# M2.net
KiCad netlist of a schematic drawn in Altium Designer
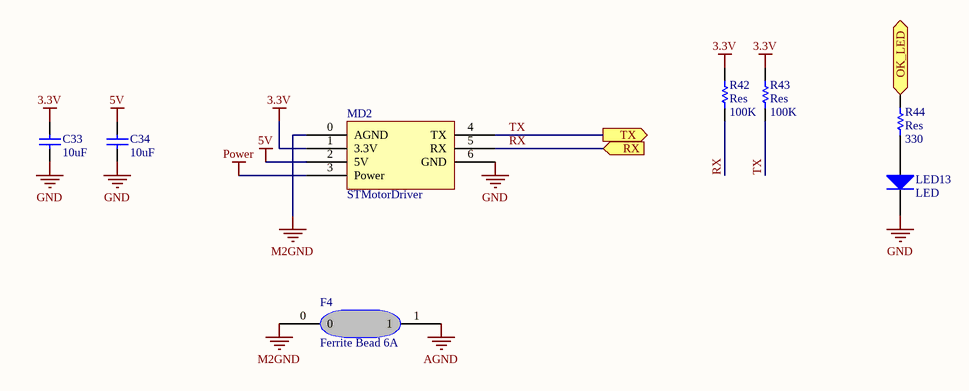
[diagram p0: M2.SchDoc]

(export (version "E")
  (design (tool "Eeschema 10.0.6"))
  (components
    (comp (ref "C33")
      (value "10uF")
      (footprint "2012[0805]")
      (description "Capacitor")
      (fields (field (name "Comment") "Cap_UP") (field (name "PUBLISHER") "Altium Limited"))
      (libsource (lib "KN2CLib") (part "Cap_UP"))
    )
    (comp (ref "C34")
      (value "10uF")
      (footprint "2012[0805]")
      (description "Capacitor")
      (fields (field (name "Comment") "Cap_UP") (field (name "PUBLISHER") "Altium Limited"))
      (libsource (lib "KN2CLib") (part "Cap_UP"))
    )
    (comp (ref "F4")
      (value "Ferrite Bead 6A")
      (footprint "f6A")
      (libsource (lib "Ferrite Bead") (part "F6A"))
    )
    (comp (ref "LED13")
      (value "LED")
      (footprint "2012[0805]")
      (description "1 Amp General Purpose Rectifier")
      (fields (field (name "PUBLISHER") "Altium Limited"))
      (libsource (lib "KN2CLib") (part "Diode"))
    )
    (comp (ref "MD2")
      (value "STMotorDriver")
      (footprint "MotorDriver")
      (libsource (lib "STMotorDriver") (part "STMotorDriver"))
    )
    (comp (ref "R42")
      (value "Res")
      (footprint "2012[0805]")
      (description "Semiconductor Resistor")
      (fields (field (name "ALTIUM_VALUE") "100K") (field (name "PUBLISHER") "Altium Limited"))
      (libsource (lib "KN2CLib") (part "Res"))
    )
    (comp (ref "R43")
      (value "Res")
      (footprint "2012[0805]")
      (description "Semiconductor Resistor")
      (fields (field (name "ALTIUM_VALUE") "100K") (field (name "PUBLISHER") "Altium Limited"))
      (libsource (lib "KN2CLib") (part "Res"))
    )
    (comp (ref "R44")
      (value "Res")
      (footprint "2012[0805]")
      (description "Semiconductor Resistor")
      (fields (field (name "ALTIUM_VALUE") "330") (field (name "PUBLISHER") "Altium Limited"))
      (libsource (lib "KN2CLib") (part "Res"))
    )
  )
  (nets
    (net (code "1") (name "/OK_LED") (class "Default")
      (node (ref "R44") (pin "1") (pinfunction "1_1") (pintype "passive"))
    )
    (net (code "2") (name "/RX") (class "Default")
      (node (ref "MD2") (pin "5") (pinfunction "RX_5") (pintype "passive"))
      (node (ref "R42") (pin "1") (pinfunction "1_1") (pintype "passive"))
    )
    (net (code "3") (name "/TX") (class "Default")
      (node (ref "MD2") (pin "4") (pinfunction "TX_4") (pintype "passive"))
      (node (ref "R43") (pin "1") (pinfunction "1_1") (pintype "passive"))
    )
    (net (code "4") (name "3.3V") (class "Default")
      (node (ref "C33") (pin "2") (pinfunction "2_2") (pintype "passive"))
      (node (ref "MD2") (pin "1") (pinfunction "3.3V_1") (pintype "passive"))
      (node (ref "R42") (pin "2") (pinfunction "2_2") (pintype "passive"))
      (node (ref "R43") (pin "2") (pinfunction "2_2") (pintype "passive"))
    )
    (net (code "5") (name "5V") (class "Default")
      (node (ref "C34") (pin "2") (pinfunction "2_2") (pintype "passive"))
      (node (ref "MD2") (pin "2") (pinfunction "5V_2") (pintype "passive"))
    )
    (net (code "6") (name "AGND") (class "Default")
      (node (ref "F4") (pin "1") (pinfunction "1_1") (pintype "passive"))
    )
    (net (code "7") (name "GND") (class "Default")
      (node (ref "C33") (pin "1") (pinfunction "1_1") (pintype "passive"))
      (node (ref "C34") (pin "1") (pinfunction "1_1") (pintype "passive"))
      (node (ref "LED13") (pin "2") (pinfunction "K_2") (pintype "passive"))
      (node (ref "MD2") (pin "6") (pinfunction "GND_6") (pintype "passive"))
    )
    (net (code "8") (name "M2GND") (class "Default")
      (node (ref "F4") (pin "0") (pinfunction "0_0") (pintype "passive"))
      (node (ref "MD2") (pin "0") (pinfunction "AGND_0") (pintype "passive"))
    )
    (net (code "9") (name "Net-(LED13-A)") (class "Default")
      (node (ref "LED13") (pin "1") (pinfunction "A_1") (pintype "passive"))
      (node (ref "R44") (pin "2") (pinfunction "2_2") (pintype "passive"))
    )
    (net (code "10") (name "Power") (class "Default")
      (node (ref "MD2") (pin "3") (pinfunction "Power_3") (pintype "passive"))
    )
  )
)
